# LED_CONTROL.net
KiCad netlist of a schematic drawn in Altium Designer
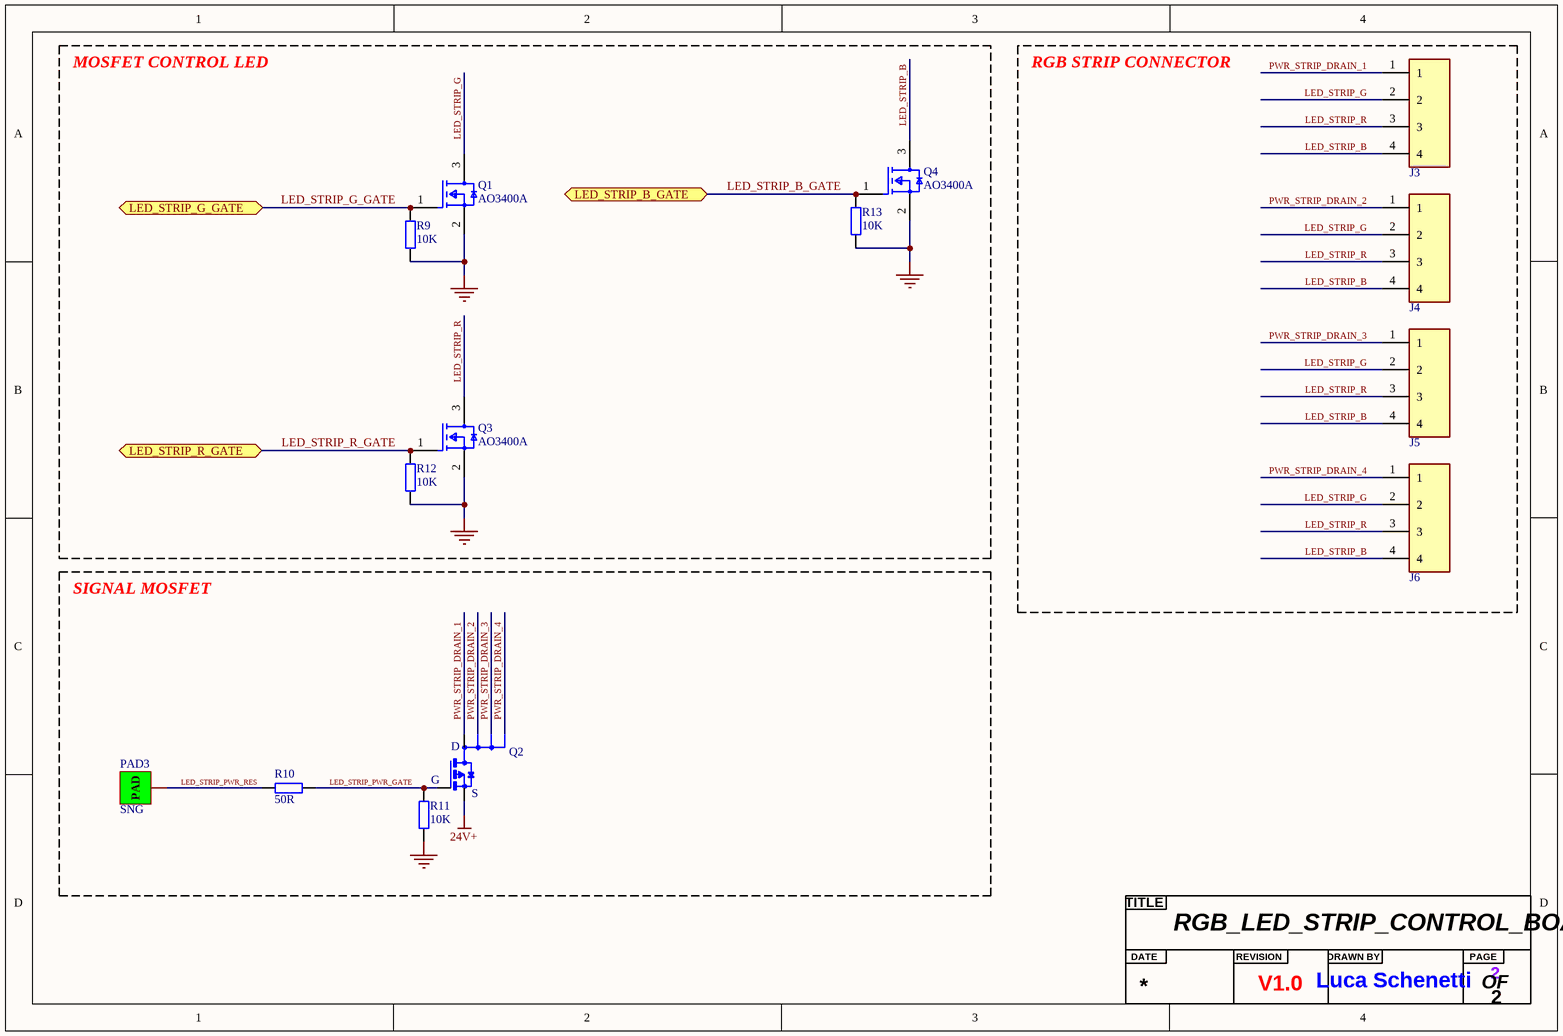
[diagram p0: LED_CONTROL.SchDoc]

(export (version "E")
  (design (tool "Eeschema 10.0.6"))
  (components
    (comp (ref "J3") (value "~") (footprint "JST_PH_CONN") (libsource (lib "SchedaLed") (part "JST_PH_CONN")))
    (comp (ref "J4") (value "~") (footprint "JST_PH_CONN") (libsource (lib "SchedaLed") (part "JST_PH_CONN")))
    (comp (ref "J5") (value "~") (footprint "JST_PH_CONN") (libsource (lib "SchedaLed") (part "JST_PH_CONN")))
    (comp (ref "J6") (value "~") (footprint "JST_PH_CONN") (libsource (lib "SchedaLed") (part "JST_PH_CONN")))
    (comp (ref "PAD3") (value "SNG") (footprint "PAD_SNG") (libsource (lib "SchedaLed") (part "PAD_SNG")))
    (comp (ref "Q1")
      (value "AO3400A")
      (footprint "FP-SOT23-MFG")
      (description "MOSFET N-CH 30V 5.7A SOT23\r\n[C20917]")
      (libsource (lib "Altium Content Vault") (part "0a9ea7c96deaaede766a5b531c28de0"))
    )
    (comp (ref "Q2")
      (value "FDC610PZ")
      (footprint "FDC610PZ")
      (libsource (lib "SchedaLed") (part "FDC610PZ"))
    )
    (comp (ref "Q3")
      (value "AO3400A")
      (footprint "FP-SOT23-MFG")
      (description "MOSFET N-CH 30V 5.7A SOT23\r\n[C20917]")
      (libsource (lib "Altium Content Vault") (part "0a9ea7c96deaaede766a5b531c28de0"))
    )
    (comp (ref "Q4")
      (value "AO3400A")
      (footprint "FP-SOT23-MFG")
      (description "MOSFET N-CH 30V 5.7A SOT23\r\n[C20917]")
      (libsource (lib "Altium Content Vault") (part "0a9ea7c96deaaede766a5b531c28de0"))
    )
    (comp (ref "R9")
      (value "10K")
      (footprint "RES_0402")
      (description "Resistor SMD 0402 [C25744]")
      (libsource (lib "Schematic-Lib-PhilsLab") (part "RES_0402"))
    )
    (comp (ref "R10")
      (value "50R")
      (footprint "RES_0603")
      (description "Resistor SMD 0603[C849792]")
      (libsource (lib "Schematic-Lib-PhilsLab") (part "RES_0603"))
    )
    (comp (ref "R11")
      (value "10K")
      (footprint "RES_0402")
      (description "Resistor SMD 0402 [C25744]")
      (libsource (lib "Schematic-Lib-PhilsLab") (part "RES_0402"))
    )
    (comp (ref "R12")
      (value "10K")
      (footprint "RES_0402")
      (description "Resistor SMD 0402 [C25744]")
      (libsource (lib "Schematic-Lib-PhilsLab") (part "RES_0402"))
    )
    (comp (ref "R13")
      (value "10K")
      (footprint "RES_0402")
      (description "Resistor SMD 0402 [C25744]")
      (libsource (lib "Schematic-Lib-PhilsLab") (part "RES_0402"))
    )
  )
  (nets
    (net (code "1") (name "/LED_STRIP_B") (class "Default")
      (node (ref "J3") (pin "4") (pinfunction "4_4") (pintype "passive"))
      (node (ref "J4") (pin "4") (pinfunction "4_4") (pintype "passive"))
      (node (ref "J5") (pin "4") (pinfunction "4_4") (pintype "passive"))
      (node (ref "J6") (pin "4") (pinfunction "4_4") (pintype "passive"))
      (node (ref "Q4") (pin "3") (pinfunction "D_3") (pintype "passive"))
    )
    (net (code "2") (name "/LED_STRIP_B_GATE") (class "Default")
      (node (ref "Q4") (pin "1") (pinfunction "G_1") (pintype "passive"))
      (node (ref "R13") (pin "2") (pinfunction "2_2") (pintype "passive"))
    )
    (net (code "3") (name "/LED_STRIP_G") (class "Default")
      (node (ref "J3") (pin "2") (pinfunction "2_2") (pintype "passive"))
      (node (ref "J4") (pin "2") (pinfunction "2_2") (pintype "passive"))
      (node (ref "J5") (pin "2") (pinfunction "2_2") (pintype "passive"))
      (node (ref "J6") (pin "2") (pinfunction "2_2") (pintype "passive"))
      (node (ref "Q1") (pin "3") (pinfunction "D_3") (pintype "passive"))
    )
    (net (code "4") (name "/LED_STRIP_G_GATE") (class "Default")
      (node (ref "Q1") (pin "1") (pinfunction "G_1") (pintype "passive"))
      (node (ref "R9") (pin "2") (pinfunction "2_2") (pintype "passive"))
    )
    (net (code "5") (name "/LED_STRIP_PWR_GATE") (class "Default")
      (node (ref "Q2") (pin "3") (pinfunction "G_3") (pintype "passive"))
      (node (ref "R10") (pin "2") (pinfunction "2_2") (pintype "passive"))
      (node (ref "R11") (pin "2") (pinfunction "2_2") (pintype "passive"))
    )
    (net (code "6") (name "/LED_STRIP_PWR_RES") (class "Default")
      (node (ref "PAD3") (pin "1") (pinfunction "PAD_1") (pintype "passive"))
      (node (ref "R10") (pin "1") (pinfunction "1_1") (pintype "passive"))
    )
    (net (code "7") (name "/LED_STRIP_R") (class "Default")
      (node (ref "J3") (pin "3") (pinfunction "3_3") (pintype "passive"))
      (node (ref "J4") (pin "3") (pinfunction "3_3") (pintype "passive"))
      (node (ref "J5") (pin "3") (pinfunction "3_3") (pintype "passive"))
      (node (ref "J6") (pin "3") (pinfunction "3_3") (pintype "passive"))
      (node (ref "Q3") (pin "3") (pinfunction "D_3") (pintype "passive"))
    )
    (net (code "8") (name "/LED_STRIP_R_GATE") (class "Default")
      (node (ref "Q3") (pin "1") (pinfunction "G_1") (pintype "passive"))
      (node (ref "R12") (pin "2") (pinfunction "2_2") (pintype "passive"))
    )
    (net (code "9") (name "/PWR_STRIP_DRAIN_1") (class "Default")
      (node (ref "J3") (pin "1") (pinfunction "1_1") (pintype "passive"))
      (node (ref "Q2") (pin "1") (pinfunction "D1_1") (pintype "passive"))
    )
    (net (code "10") (name "/PWR_STRIP_DRAIN_2") (class "Default")
      (node (ref "J4") (pin "1") (pinfunction "1_1") (pintype "passive"))
      (node (ref "Q2") (pin "2") (pinfunction "D2_2") (pintype "passive"))
    )
    (net (code "11") (name "/PWR_STRIP_DRAIN_3") (class "Default")
      (node (ref "J5") (pin "1") (pinfunction "1_1") (pintype "passive"))
      (node (ref "Q2") (pin "6") (pinfunction "D3_6") (pintype "passive"))
    )
    (net (code "12") (name "/PWR_STRIP_DRAIN_4") (class "Default")
      (node (ref "J6") (pin "1") (pinfunction "1_1") (pintype "passive"))
      (node (ref "Q2") (pin "5") (pinfunction "D4_5") (pintype "passive"))
    )
    (net (code "13") (name "24V+") (class "Default")
      (node (ref "Q2") (pin "4") (pinfunction "S_4") (pintype "passive"))
    )
    (net (code "14") (name "GND") (class "Default")
      (node (ref "Q1") (pin "2") (pinfunction "S_2") (pintype "passive"))
      (node (ref "Q3") (pin "2") (pinfunction "S_2") (pintype "passive"))
      (node (ref "Q4") (pin "2") (pinfunction "S_2") (pintype "passive"))
      (node (ref "R11") (pin "1") (pinfunction "1_1") (pintype "passive"))
      (node (ref "R12") (pin "1") (pinfunction "1_1") (pintype "passive"))
      (node (ref "R13") (pin "1") (pinfunction "1_1") (pintype "passive"))
      (node (ref "R9") (pin "1") (pinfunction "1_1") (pintype "passive"))
    )
  )
)
